# ProPrj_USB_Hub_2026-05-31.net
KiCad netlist of a schematic drawn in EasyEDA Pro
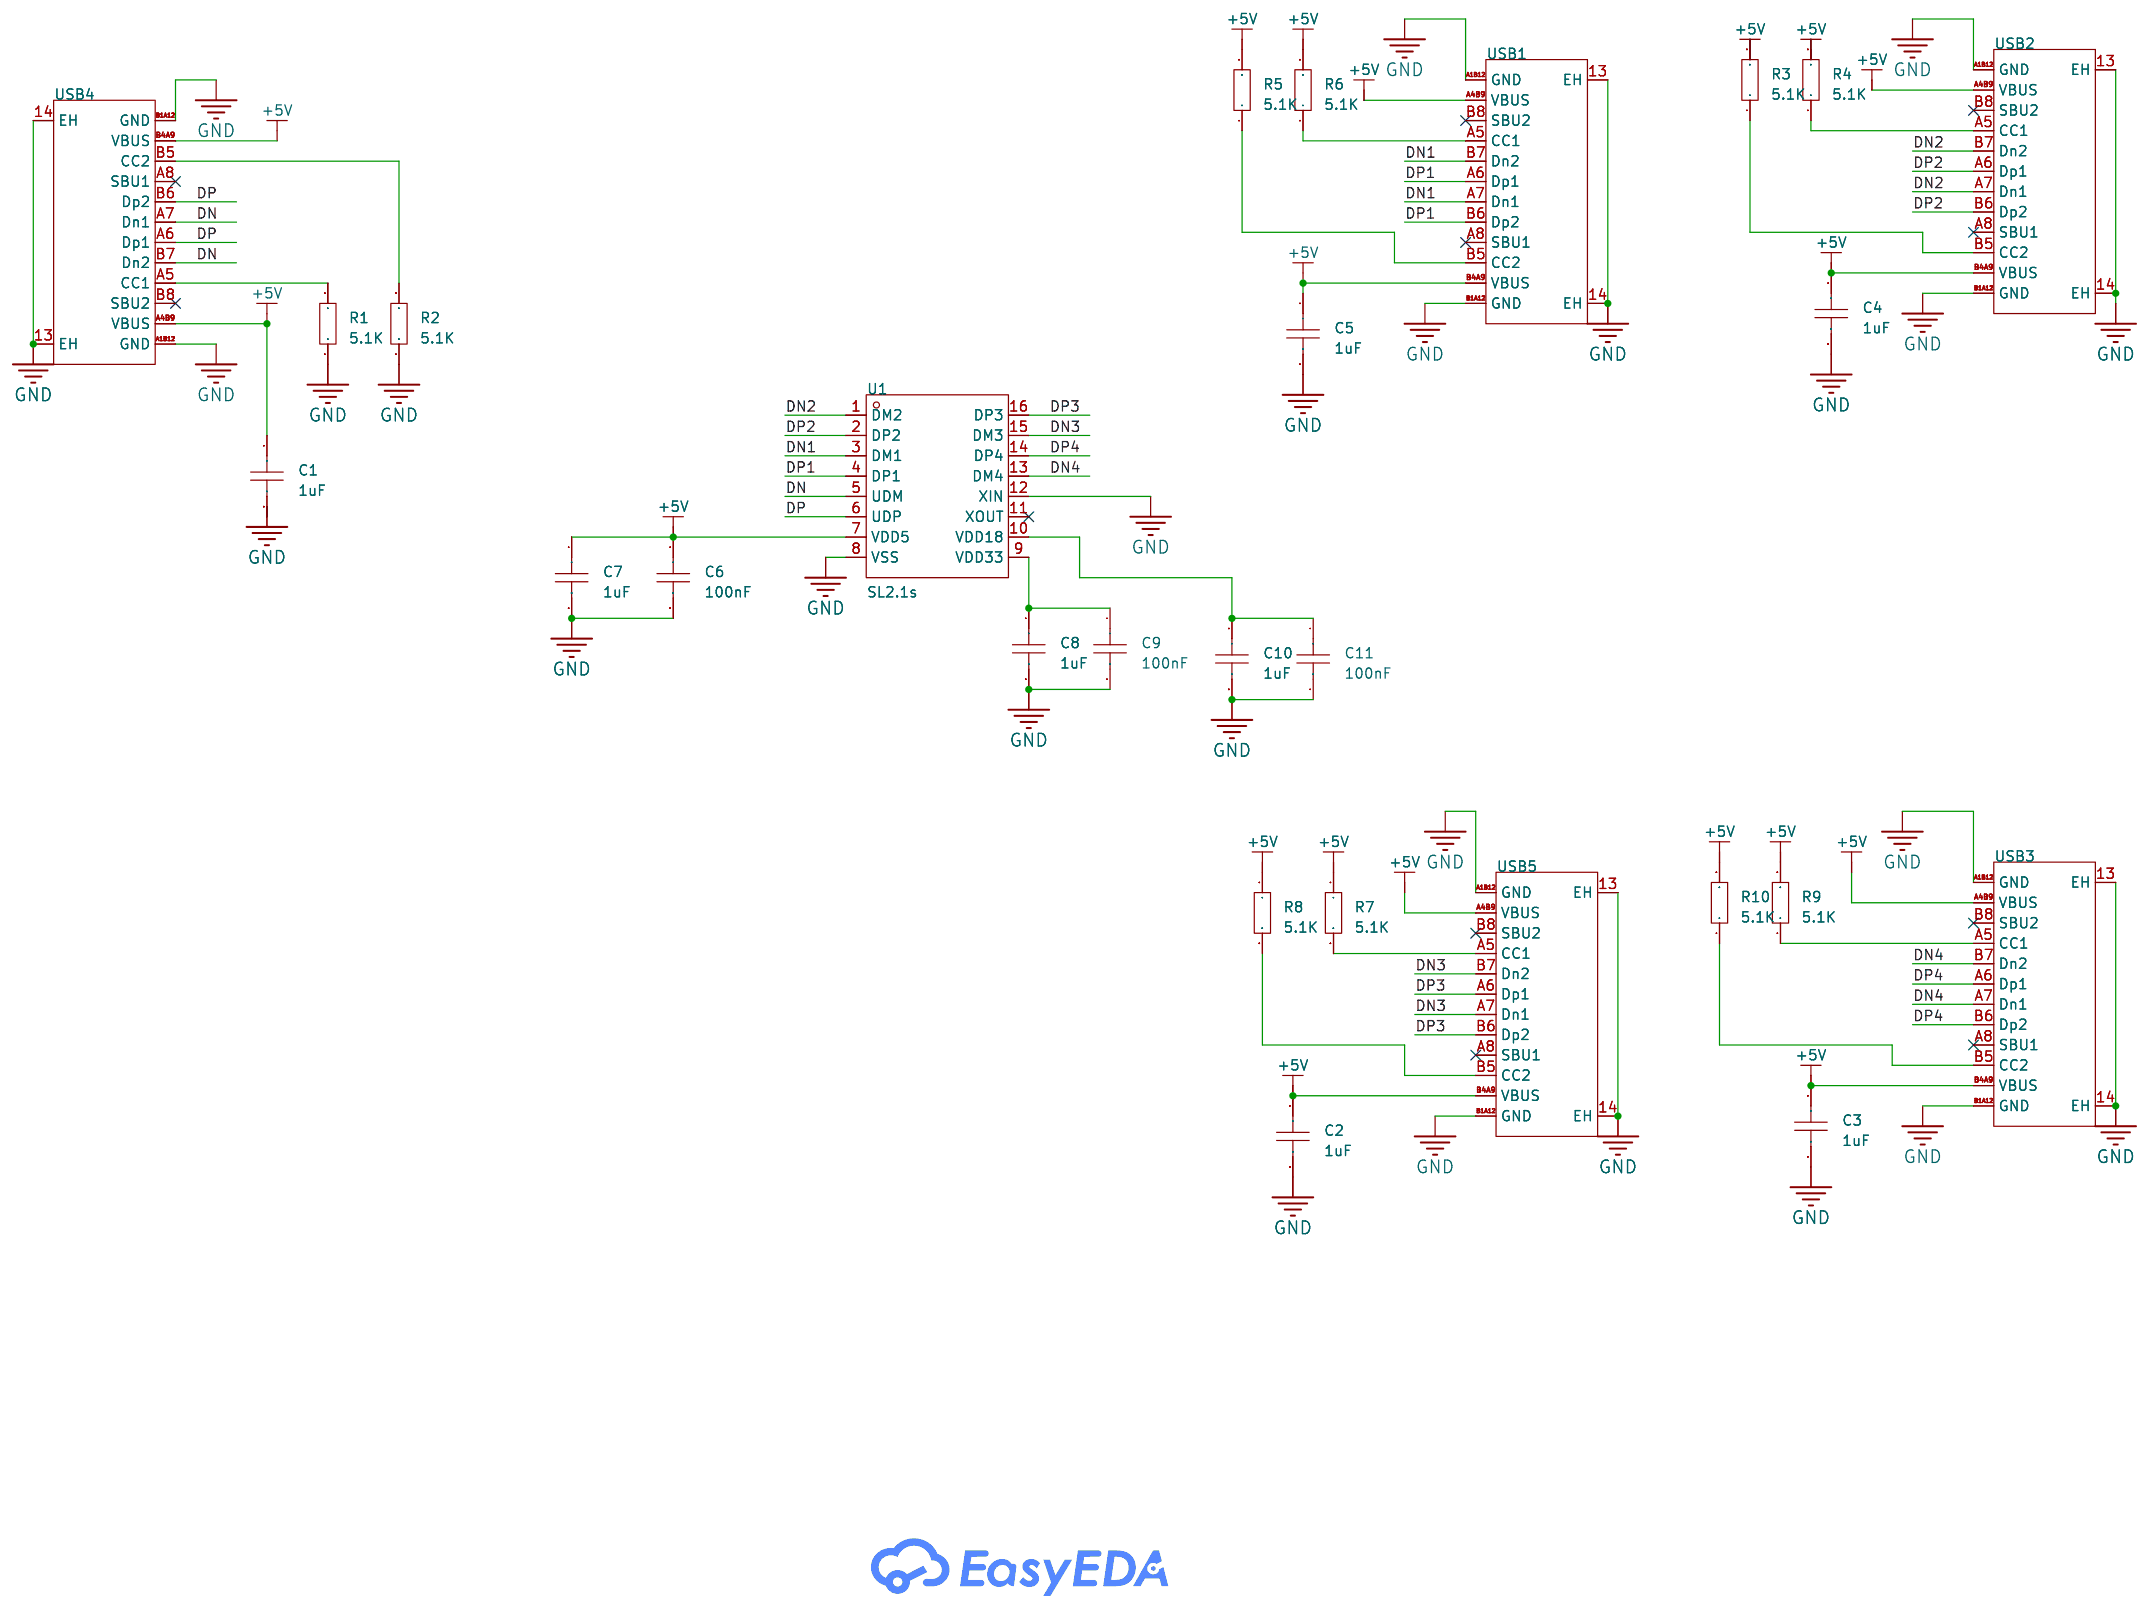
[diagram p0: schematic sheet]

(export (version "E")
  (design (tool "Eeschema 10.0.6"))
  (components
    (comp (ref "C1") (value "1uF") (footprint "easyedapro:C0603") (libsource (lib "easyedapro") (part "CAP")))
    (comp (ref "C2") (value "1uF") (footprint "easyedapro:C0603") (libsource (lib "easyedapro") (part "CAP")))
    (comp (ref "C3") (value "1uF") (footprint "easyedapro:C0603") (libsource (lib "easyedapro") (part "CAP")))
    (comp (ref "C4") (value "1uF") (footprint "easyedapro:C0603") (libsource (lib "easyedapro") (part "CAP")))
    (comp (ref "C5") (value "1uF") (footprint "easyedapro:C0603") (libsource (lib "easyedapro") (part "CAP")))
    (comp (ref "C6")
      (value "100nF")
      (footprint "easyedapro:C0603")
      (libsource (lib "easyedapro") (part "CAP"))
    )
    (comp (ref "C7") (value "1uF") (footprint "easyedapro:C0603") (libsource (lib "easyedapro") (part "CAP")))
    (comp (ref "C8") (value "1uF") (footprint "easyedapro:C0603") (libsource (lib "easyedapro") (part "CAP")))
    (comp (ref "C9")
      (value "100nF")
      (footprint "easyedapro:C0603")
      (libsource (lib "easyedapro") (part "CAP"))
    )
    (comp (ref "C10")
      (value "1uF")
      (footprint "easyedapro:C0603")
      (libsource (lib "easyedapro") (part "CAP"))
    )
    (comp (ref "C11")
      (value "100nF")
      (footprint "easyedapro:C0603")
      (libsource (lib "easyedapro") (part "CAP"))
    )
    (comp (ref "R1")
      (value "5.1K")
      (footprint "easyedapro:R0603")
      (libsource (lib "easyedapro") (part "Res"))
    )
    (comp (ref "R2")
      (value "5.1K")
      (footprint "easyedapro:R0603")
      (libsource (lib "easyedapro") (part "Res"))
    )
    (comp (ref "R3")
      (value "5.1K")
      (footprint "easyedapro:R0603")
      (libsource (lib "easyedapro") (part "Res"))
    )
    (comp (ref "R4")
      (value "5.1K")
      (footprint "easyedapro:R0603")
      (libsource (lib "easyedapro") (part "Res"))
    )
    (comp (ref "R5")
      (value "5.1K")
      (footprint "easyedapro:R0603")
      (libsource (lib "easyedapro") (part "Res"))
    )
    (comp (ref "R6")
      (value "5.1K")
      (footprint "easyedapro:R0603")
      (libsource (lib "easyedapro") (part "Res"))
    )
    (comp (ref "R7")
      (value "5.1K")
      (footprint "easyedapro:R0603")
      (libsource (lib "easyedapro") (part "Res"))
    )
    (comp (ref "R8")
      (value "5.1K")
      (footprint "easyedapro:R0603")
      (libsource (lib "easyedapro") (part "Res"))
    )
    (comp (ref "R9")
      (value "5.1K")
      (footprint "easyedapro:R0603")
      (libsource (lib "easyedapro") (part "Res"))
    )
    (comp (ref "R10")
      (value "5.1K")
      (footprint "easyedapro:R0603")
      (libsource (lib "easyedapro") (part "Res"))
    )
    (comp (ref "U1")
      (value "SL2.1s")
      (footprint "easyedapro:SSOP-16_L4.6-W2.6-P0.53-LS4.0-BL")
      (fields (field (name "Manufacturer") "CoreChips(和芯润德)"))
      (libsource (lib "easyedapro") (part "SL2.1S"))
    )
    (comp (ref "USB1")
      (value "TYPE-C 16PIN 2MD(073)")
      (footprint "easyedapro:USB-C-SMD_TYPE-C-16PIN-2MD-073")
      (fields (field (name "Manufacturer") "SHOU HAN(首韩)"))
      (libsource (lib "easyedapro") (part "TYPE-C 16PIN 2MD(073)"))
    )
    (comp (ref "USB2")
      (value "TYPE-C 16PIN 2MD(073)")
      (footprint "easyedapro:USB-C-SMD_TYPE-C-16PIN-2MD-073")
      (fields (field (name "Manufacturer") "SHOU HAN(首韩)"))
      (libsource (lib "easyedapro") (part "TYPE-C 16PIN 2MD(073)"))
    )
    (comp (ref "USB3")
      (value "TYPE-C 16PIN 2MD(073)")
      (footprint "easyedapro:USB-C-SMD_TYPE-C-16PIN-2MD-073")
      (fields (field (name "Manufacturer") "SHOU HAN(首韩)"))
      (libsource (lib "easyedapro") (part "TYPE-C 16PIN 2MD(073)"))
    )
    (comp (ref "USB4")
      (value "TYPE-C 16PIN 2MD(073)")
      (footprint "easyedapro:USB-C-SMD_TYPE-C-16PIN-2MD-073")
      (fields (field (name "Manufacturer") "SHOU HAN(首韩)"))
      (libsource (lib "easyedapro") (part "TYPE-C 16PIN 2MD(073)"))
    )
    (comp (ref "USB5")
      (value "TYPE-C 16PIN 2MD(073)")
      (footprint "easyedapro:USB-C-SMD_TYPE-C-16PIN-2MD-073")
      (fields (field (name "Manufacturer") "SHOU HAN(首韩)"))
      (libsource (lib "easyedapro") (part "TYPE-C 16PIN 2MD(073)"))
    )
  )
  (nets
    (net (code "1") (name "+5V") (class "Default")
      (node (ref "C1") (pin "1") (pinfunction "1_1") (pintype "input"))
      (node (ref "C2") (pin "1") (pinfunction "1_1") (pintype "input"))
      (node (ref "C3") (pin "1") (pinfunction "1_1") (pintype "input"))
      (node (ref "C4") (pin "1") (pinfunction "1_1") (pintype "input"))
      (node (ref "C5") (pin "1") (pinfunction "1_1") (pintype "input"))
      (node (ref "C6") (pin "1") (pinfunction "1_1") (pintype "input"))
      (node (ref "C7") (pin "1") (pinfunction "1_1") (pintype "input"))
      (node (ref "R10") (pin "2") (pinfunction "2_2") (pintype "input"))
      (node (ref "R3") (pin "2") (pinfunction "2_2") (pintype "input"))
      (node (ref "R4") (pin "2") (pinfunction "2_2") (pintype "input"))
      (node (ref "R5") (pin "2") (pinfunction "2_2") (pintype "input"))
      (node (ref "R6") (pin "2") (pinfunction "2_2") (pintype "input"))
      (node (ref "R7") (pin "1") (pinfunction "1_1") (pintype "input"))
      (node (ref "R8") (pin "1") (pinfunction "1_1") (pintype "input"))
      (node (ref "R9") (pin "2") (pinfunction "2_2") (pintype "input"))
      (node (ref "U1") (pin "7") (pinfunction "VDD5_7") (pintype "unspecified"))
      (node (ref "USB1") (pin "A4B9") (pinfunction "VBUS_A4B9") (pintype "unspecified"))
      (node (ref "USB1") (pin "B4A9") (pinfunction "VBUS_B4A9") (pintype "unspecified"))
      (node (ref "USB2") (pin "A4B9") (pinfunction "VBUS_A4B9") (pintype "unspecified"))
      (node (ref "USB2") (pin "B4A9") (pinfunction "VBUS_B4A9") (pintype "unspecified"))
      (node (ref "USB3") (pin "A4B9") (pinfunction "VBUS_A4B9") (pintype "unspecified"))
      (node (ref "USB3") (pin "B4A9") (pinfunction "VBUS_B4A9") (pintype "unspecified"))
      (node (ref "USB4") (pin "A4B9") (pinfunction "VBUS_A4B9") (pintype "unspecified"))
      (node (ref "USB4") (pin "B4A9") (pinfunction "VBUS_B4A9") (pintype "unspecified"))
      (node (ref "USB5") (pin "A4B9") (pinfunction "VBUS_A4B9") (pintype "unspecified"))
      (node (ref "USB5") (pin "B4A9") (pinfunction "VBUS_B4A9") (pintype "unspecified"))
    )
    (net (code "2") (name "/DN") (class "Default")
      (node (ref "U1") (pin "5") (pinfunction "UDM_5") (pintype "unspecified"))
      (node (ref "USB4") (pin "A7") (pinfunction "Dn1_A7") (pintype "unspecified"))
      (node (ref "USB4") (pin "B7") (pinfunction "Dn2_B7") (pintype "unspecified"))
    )
    (net (code "3") (name "/DN1") (class "Default")
      (node (ref "U1") (pin "3") (pinfunction "DM1_3") (pintype "unspecified"))
      (node (ref "USB1") (pin "A7") (pinfunction "Dn1_A7") (pintype "unspecified"))
      (node (ref "USB1") (pin "B7") (pinfunction "Dn2_B7") (pintype "unspecified"))
    )
    (net (code "4") (name "/DN2") (class "Default")
      (node (ref "U1") (pin "1") (pinfunction "DM2_1") (pintype "unspecified"))
      (node (ref "USB2") (pin "A7") (pinfunction "Dn1_A7") (pintype "unspecified"))
      (node (ref "USB2") (pin "B7") (pinfunction "Dn2_B7") (pintype "unspecified"))
    )
    (net (code "5") (name "/DN3") (class "Default")
      (node (ref "U1") (pin "15") (pinfunction "DM3_15") (pintype "unspecified"))
      (node (ref "USB5") (pin "A7") (pinfunction "Dn1_A7") (pintype "unspecified"))
      (node (ref "USB5") (pin "B7") (pinfunction "Dn2_B7") (pintype "unspecified"))
    )
    (net (code "6") (name "/DN4") (class "Default")
      (node (ref "U1") (pin "13") (pinfunction "DM4_13") (pintype "unspecified"))
      (node (ref "USB3") (pin "A7") (pinfunction "Dn1_A7") (pintype "unspecified"))
      (node (ref "USB3") (pin "B7") (pinfunction "Dn2_B7") (pintype "unspecified"))
    )
    (net (code "7") (name "/DP") (class "Default")
      (node (ref "U1") (pin "6") (pinfunction "UDP_6") (pintype "unspecified"))
      (node (ref "USB4") (pin "A6") (pinfunction "Dp1_A6") (pintype "unspecified"))
      (node (ref "USB4") (pin "B6") (pinfunction "Dp2_B6") (pintype "unspecified"))
    )
    (net (code "8") (name "/DP1") (class "Default")
      (node (ref "U1") (pin "4") (pinfunction "DP1_4") (pintype "unspecified"))
      (node (ref "USB1") (pin "A6") (pinfunction "Dp1_A6") (pintype "unspecified"))
      (node (ref "USB1") (pin "B6") (pinfunction "Dp2_B6") (pintype "unspecified"))
    )
    (net (code "9") (name "/DP2") (class "Default")
      (node (ref "U1") (pin "2") (pinfunction "DP2_2") (pintype "unspecified"))
      (node (ref "USB2") (pin "A6") (pinfunction "Dp1_A6") (pintype "unspecified"))
      (node (ref "USB2") (pin "B6") (pinfunction "Dp2_B6") (pintype "unspecified"))
    )
    (net (code "10") (name "/DP3") (class "Default")
      (node (ref "U1") (pin "16") (pinfunction "DP3_16") (pintype "unspecified"))
      (node (ref "USB5") (pin "A6") (pinfunction "Dp1_A6") (pintype "unspecified"))
      (node (ref "USB5") (pin "B6") (pinfunction "Dp2_B6") (pintype "unspecified"))
    )
    (net (code "11") (name "/DP4") (class "Default")
      (node (ref "U1") (pin "14") (pinfunction "DP4_14") (pintype "unspecified"))
      (node (ref "USB3") (pin "A6") (pinfunction "Dp1_A6") (pintype "unspecified"))
      (node (ref "USB3") (pin "B6") (pinfunction "Dp2_B6") (pintype "unspecified"))
    )
    (net (code "12") (name "GND") (class "Default")
      (node (ref "C1") (pin "2") (pinfunction "2_2") (pintype "input"))
      (node (ref "C10") (pin "2") (pinfunction "2_2") (pintype "input"))
      (node (ref "C11") (pin "2") (pinfunction "2_2") (pintype "input"))
      (node (ref "C2") (pin "2") (pinfunction "2_2") (pintype "input"))
      (node (ref "C3") (pin "2") (pinfunction "2_2") (pintype "input"))
      (node (ref "C4") (pin "2") (pinfunction "2_2") (pintype "input"))
      (node (ref "C5") (pin "2") (pinfunction "2_2") (pintype "input"))
      (node (ref "C6") (pin "2") (pinfunction "2_2") (pintype "input"))
      (node (ref "C7") (pin "2") (pinfunction "2_2") (pintype "input"))
      (node (ref "C8") (pin "2") (pinfunction "2_2") (pintype "input"))
      (node (ref "C9") (pin "2") (pinfunction "2_2") (pintype "input"))
      (node (ref "R1") (pin "1") (pinfunction "1_1") (pintype "input"))
      (node (ref "R2") (pin "1") (pinfunction "1_1") (pintype "input"))
      (node (ref "U1") (pin "12") (pinfunction "XIN_12") (pintype "unspecified"))
      (node (ref "U1") (pin "8") (pinfunction "VSS_8") (pintype "unspecified"))
      (node (ref "USB1") (pin "13") (pinfunction "EH_13") (pintype "unspecified"))
      (node (ref "USB1") (pin "14") (pinfunction "EH_14") (pintype "unspecified"))
      (node (ref "USB1") (pin "A1B12") (pinfunction "GND_A1B12") (pintype "unspecified"))
      (node (ref "USB1") (pin "B1A12") (pinfunction "GND_B1A12") (pintype "unspecified"))
      (node (ref "USB2") (pin "13") (pinfunction "EH_13") (pintype "unspecified"))
      (node (ref "USB2") (pin "14") (pinfunction "EH_14") (pintype "unspecified"))
      (node (ref "USB2") (pin "A1B12") (pinfunction "GND_A1B12") (pintype "unspecified"))
      (node (ref "USB2") (pin "B1A12") (pinfunction "GND_B1A12") (pintype "unspecified"))
      (node (ref "USB3") (pin "13") (pinfunction "EH_13") (pintype "unspecified"))
      (node (ref "USB3") (pin "14") (pinfunction "EH_14") (pintype "unspecified"))
      (node (ref "USB3") (pin "A1B12") (pinfunction "GND_A1B12") (pintype "unspecified"))
      (node (ref "USB3") (pin "B1A12") (pinfunction "GND_B1A12") (pintype "unspecified"))
      (node (ref "USB4") (pin "13") (pinfunction "EH_13") (pintype "unspecified"))
      (node (ref "USB4") (pin "14") (pinfunction "EH_14") (pintype "unspecified"))
      (node (ref "USB4") (pin "A1B12") (pinfunction "GND_A1B12") (pintype "unspecified"))
      (node (ref "USB4") (pin "B1A12") (pinfunction "GND_B1A12") (pintype "unspecified"))
      (node (ref "USB5") (pin "13") (pinfunction "EH_13") (pintype "unspecified"))
      (node (ref "USB5") (pin "14") (pinfunction "EH_14") (pintype "unspecified"))
      (node (ref "USB5") (pin "A1B12") (pinfunction "GND_A1B12") (pintype "unspecified"))
      (node (ref "USB5") (pin "B1A12") (pinfunction "GND_B1A12") (pintype "unspecified"))
    )
    (net (code "13") (name "Net-(U1-VDD18)") (class "Default")
      (node (ref "C10") (pin "1") (pinfunction "1_1") (pintype "input"))
      (node (ref "C11") (pin "1") (pinfunction "1_1") (pintype "input"))
      (node (ref "U1") (pin "10") (pinfunction "VDD18_10") (pintype "unspecified"))
    )
    (net (code "14") (name "Net-(U1-VDD33)") (class "Default")
      (node (ref "C8") (pin "1") (pinfunction "1_1") (pintype "input"))
      (node (ref "C9") (pin "1") (pinfunction "1_1") (pintype "input"))
      (node (ref "U1") (pin "9") (pinfunction "VDD33_9") (pintype "unspecified"))
    )
    (net (code "15") (name "Net-(USB1-CC1)") (class "Default")
      (node (ref "R6") (pin "1") (pinfunction "1_1") (pintype "input"))
      (node (ref "USB1") (pin "A5") (pinfunction "CC1_A5") (pintype "unspecified"))
    )
    (net (code "16") (name "Net-(USB1-CC2)") (class "Default")
      (node (ref "R5") (pin "1") (pinfunction "1_1") (pintype "input"))
      (node (ref "USB1") (pin "B5") (pinfunction "CC2_B5") (pintype "unspecified"))
    )
    (net (code "17") (name "Net-(USB2-CC1)") (class "Default")
      (node (ref "R4") (pin "1") (pinfunction "1_1") (pintype "input"))
      (node (ref "USB2") (pin "A5") (pinfunction "CC1_A5") (pintype "unspecified"))
    )
    (net (code "18") (name "Net-(USB2-CC2)") (class "Default")
      (node (ref "R3") (pin "1") (pinfunction "1_1") (pintype "input"))
      (node (ref "USB2") (pin "B5") (pinfunction "CC2_B5") (pintype "unspecified"))
    )
    (net (code "19") (name "Net-(USB3-CC1)") (class "Default")
      (node (ref "R9") (pin "1") (pinfunction "1_1") (pintype "input"))
      (node (ref "USB3") (pin "A5") (pinfunction "CC1_A5") (pintype "unspecified"))
    )
    (net (code "20") (name "Net-(USB3-CC2)") (class "Default")
      (node (ref "R10") (pin "1") (pinfunction "1_1") (pintype "input"))
      (node (ref "USB3") (pin "B5") (pinfunction "CC2_B5") (pintype "unspecified"))
    )
    (net (code "21") (name "Net-(USB4-CC1)") (class "Default")
      (node (ref "R1") (pin "2") (pinfunction "2_2") (pintype "input"))
      (node (ref "USB4") (pin "A5") (pinfunction "CC1_A5") (pintype "unspecified"))
    )
    (net (code "22") (name "Net-(USB4-CC2)") (class "Default")
      (node (ref "R2") (pin "2") (pinfunction "2_2") (pintype "input"))
      (node (ref "USB4") (pin "B5") (pinfunction "CC2_B5") (pintype "unspecified"))
    )
    (net (code "23") (name "Net-(USB5-CC1)") (class "Default")
      (node (ref "R7") (pin "2") (pinfunction "2_2") (pintype "input"))
      (node (ref "USB5") (pin "A5") (pinfunction "CC1_A5") (pintype "unspecified"))
    )
    (net (code "24") (name "Net-(USB5-CC2)") (class "Default")
      (node (ref "R8") (pin "2") (pinfunction "2_2") (pintype "input"))
      (node (ref "USB5") (pin "B5") (pinfunction "CC2_B5") (pintype "unspecified"))
    )
    (net (code "25") (name "unconnected-(U1-XOUT-Pad11)") (class "Default")
      (node (ref "U1") (pin "11") (pinfunction "XOUT_11") (pintype "unspecified+no_connect"))
    )
    (net (code "26") (name "unconnected-(USB1-SBU1-PadA8)") (class "Default")
      (node (ref "USB1") (pin "A8") (pinfunction "SBU1_A8") (pintype "unspecified+no_connect"))
    )
    (net (code "27") (name "unconnected-(USB1-SBU2-PadB8)") (class "Default")
      (node (ref "USB1") (pin "B8") (pinfunction "SBU2_B8") (pintype "unspecified+no_connect"))
    )
    (net (code "28") (name "unconnected-(USB2-SBU1-PadA8)") (class "Default")
      (node (ref "USB2") (pin "A8") (pinfunction "SBU1_A8") (pintype "unspecified+no_connect"))
    )
    (net (code "29") (name "unconnected-(USB2-SBU2-PadB8)") (class "Default")
      (node (ref "USB2") (pin "B8") (pinfunction "SBU2_B8") (pintype "unspecified+no_connect"))
    )
    (net (code "30") (name "unconnected-(USB3-SBU1-PadA8)") (class "Default")
      (node (ref "USB3") (pin "A8") (pinfunction "SBU1_A8") (pintype "unspecified+no_connect"))
    )
    (net (code "31") (name "unconnected-(USB3-SBU2-PadB8)") (class "Default")
      (node (ref "USB3") (pin "B8") (pinfunction "SBU2_B8") (pintype "unspecified+no_connect"))
    )
    (net (code "32") (name "unconnected-(USB4-SBU1-PadA8)") (class "Default")
      (node (ref "USB4") (pin "A8") (pinfunction "SBU1_A8") (pintype "unspecified+no_connect"))
    )
    (net (code "33") (name "unconnected-(USB4-SBU2-PadB8)") (class "Default")
      (node (ref "USB4") (pin "B8") (pinfunction "SBU2_B8") (pintype "unspecified+no_connect"))
    )
    (net (code "34") (name "unconnected-(USB5-SBU1-PadA8)") (class "Default")
      (node (ref "USB5") (pin "A8") (pinfunction "SBU1_A8") (pintype "unspecified+no_connect"))
    )
    (net (code "35") (name "unconnected-(USB5-SBU2-PadB8)") (class "Default")
      (node (ref "USB5") (pin "B8") (pinfunction "SBU2_B8") (pintype "unspecified+no_connect"))
    )
  )
)
